# temp.net
KiCad netlist of a schematic drawn in EAGLE
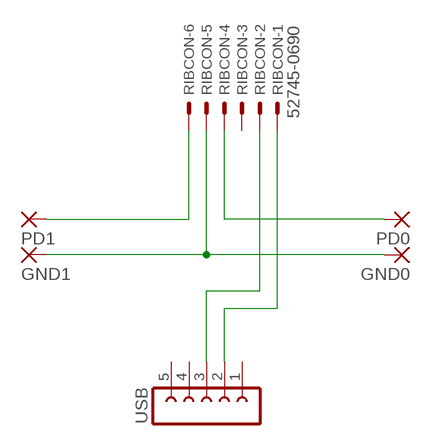
[diagram p0: schematic, sheet 1]

(export (version "E")
  (design (tool "Eeschema 10.0.6"))
  (components
    (comp (ref "GND0")
      (value "SMD5")
      (footprint "eagle-import:SMD2,54-5,08")
      (libsource (lib "eagle-import") (part "SMD5"))
    )
    (comp (ref "GND1")
      (value "SMD5")
      (footprint "eagle-import:SMD2,54-5,08")
      (libsource (lib "eagle-import") (part "SMD5"))
    )
    (comp (ref "PD0")
      (value "SMD5")
      (footprint "eagle-import:SMD2,54-5,08")
      (libsource (lib "eagle-import") (part "SMD5"))
    )
    (comp (ref "PD1")
      (value "SMD5")
      (footprint "eagle-import:SMD2,54-5,08")
      (libsource (lib "eagle-import") (part "SMD5"))
    )
    (comp (ref "RIBCON")
      (value "52745-0690")
      (footprint "eagle-import:52745-0690")
      (libsource (lib "eagle-import") (part "52745-0690"))
    )
    (comp (ref "USB")
      (value "FE05-1")
      (footprint "eagle-import:FE05-1")
      (libsource (lib "eagle-import") (part "FE05-1"))
    )
  )
  (nets
    (net (code "1") (name "Net-(GND0-P)") (class "Default")
      (node (ref "GND0") (pin "1") (pinfunction "P_1") (pintype "passive"))
      (node (ref "GND1") (pin "1") (pinfunction "P_1") (pintype "passive"))
      (node (ref "RIBCON") (pin "5") (pinfunction "S_5") (pintype "passive"))
    )
    (net (code "2") (name "Net-(PD0-P)") (class "Default")
      (node (ref "PD0") (pin "1") (pinfunction "P_1") (pintype "passive"))
      (node (ref "RIBCON") (pin "4") (pinfunction "S_4") (pintype "passive"))
    )
    (net (code "3") (name "Net-(PD1-P)") (class "Default")
      (node (ref "PD1") (pin "1") (pinfunction "P_1") (pintype "passive"))
      (node (ref "RIBCON") (pin "6") (pinfunction "S_6") (pintype "passive"))
    )
    (net (code "4") (name "Net-(RIBCONA-S)") (class "Default")
      (node (ref "RIBCON") (pin "1") (pinfunction "S_1") (pintype "passive"))
      (node (ref "USB") (pin "2") (pinfunction "2_2") (pintype "passive"))
    )
    (net (code "5") (name "Net-(RIBCONB-S)") (class "Default")
      (node (ref "RIBCON") (pin "2") (pinfunction "S_2") (pintype "passive"))
      (node (ref "USB") (pin "3") (pinfunction "3_3") (pintype "passive"))
    )
    (net (code "6") (name "unconnected-(RIBCONC-S-Pad3)") (class "Default")
      (node (ref "RIBCON") (pin "3") (pinfunction "S_3") (pintype "passive"))
    )
    (net (code "7") (name "unconnected-(USB-Pad1)") (class "Default")
      (node (ref "USB") (pin "1") (pinfunction "1_1") (pintype "passive"))
    )
    (net (code "8") (name "unconnected-(USB-Pad4)") (class "Default")
      (node (ref "USB") (pin "4") (pinfunction "4_4") (pintype "passive"))
    )
    (net (code "9") (name "unconnected-(USB-Pad5)") (class "Default")
      (node (ref "USB") (pin "5") (pinfunction "5_5") (pintype "passive"))
    )
  )
)
